# 1-Schematic_KANDA_WEATHER.net
KiCad netlist of a schematic drawn in EasyEDA
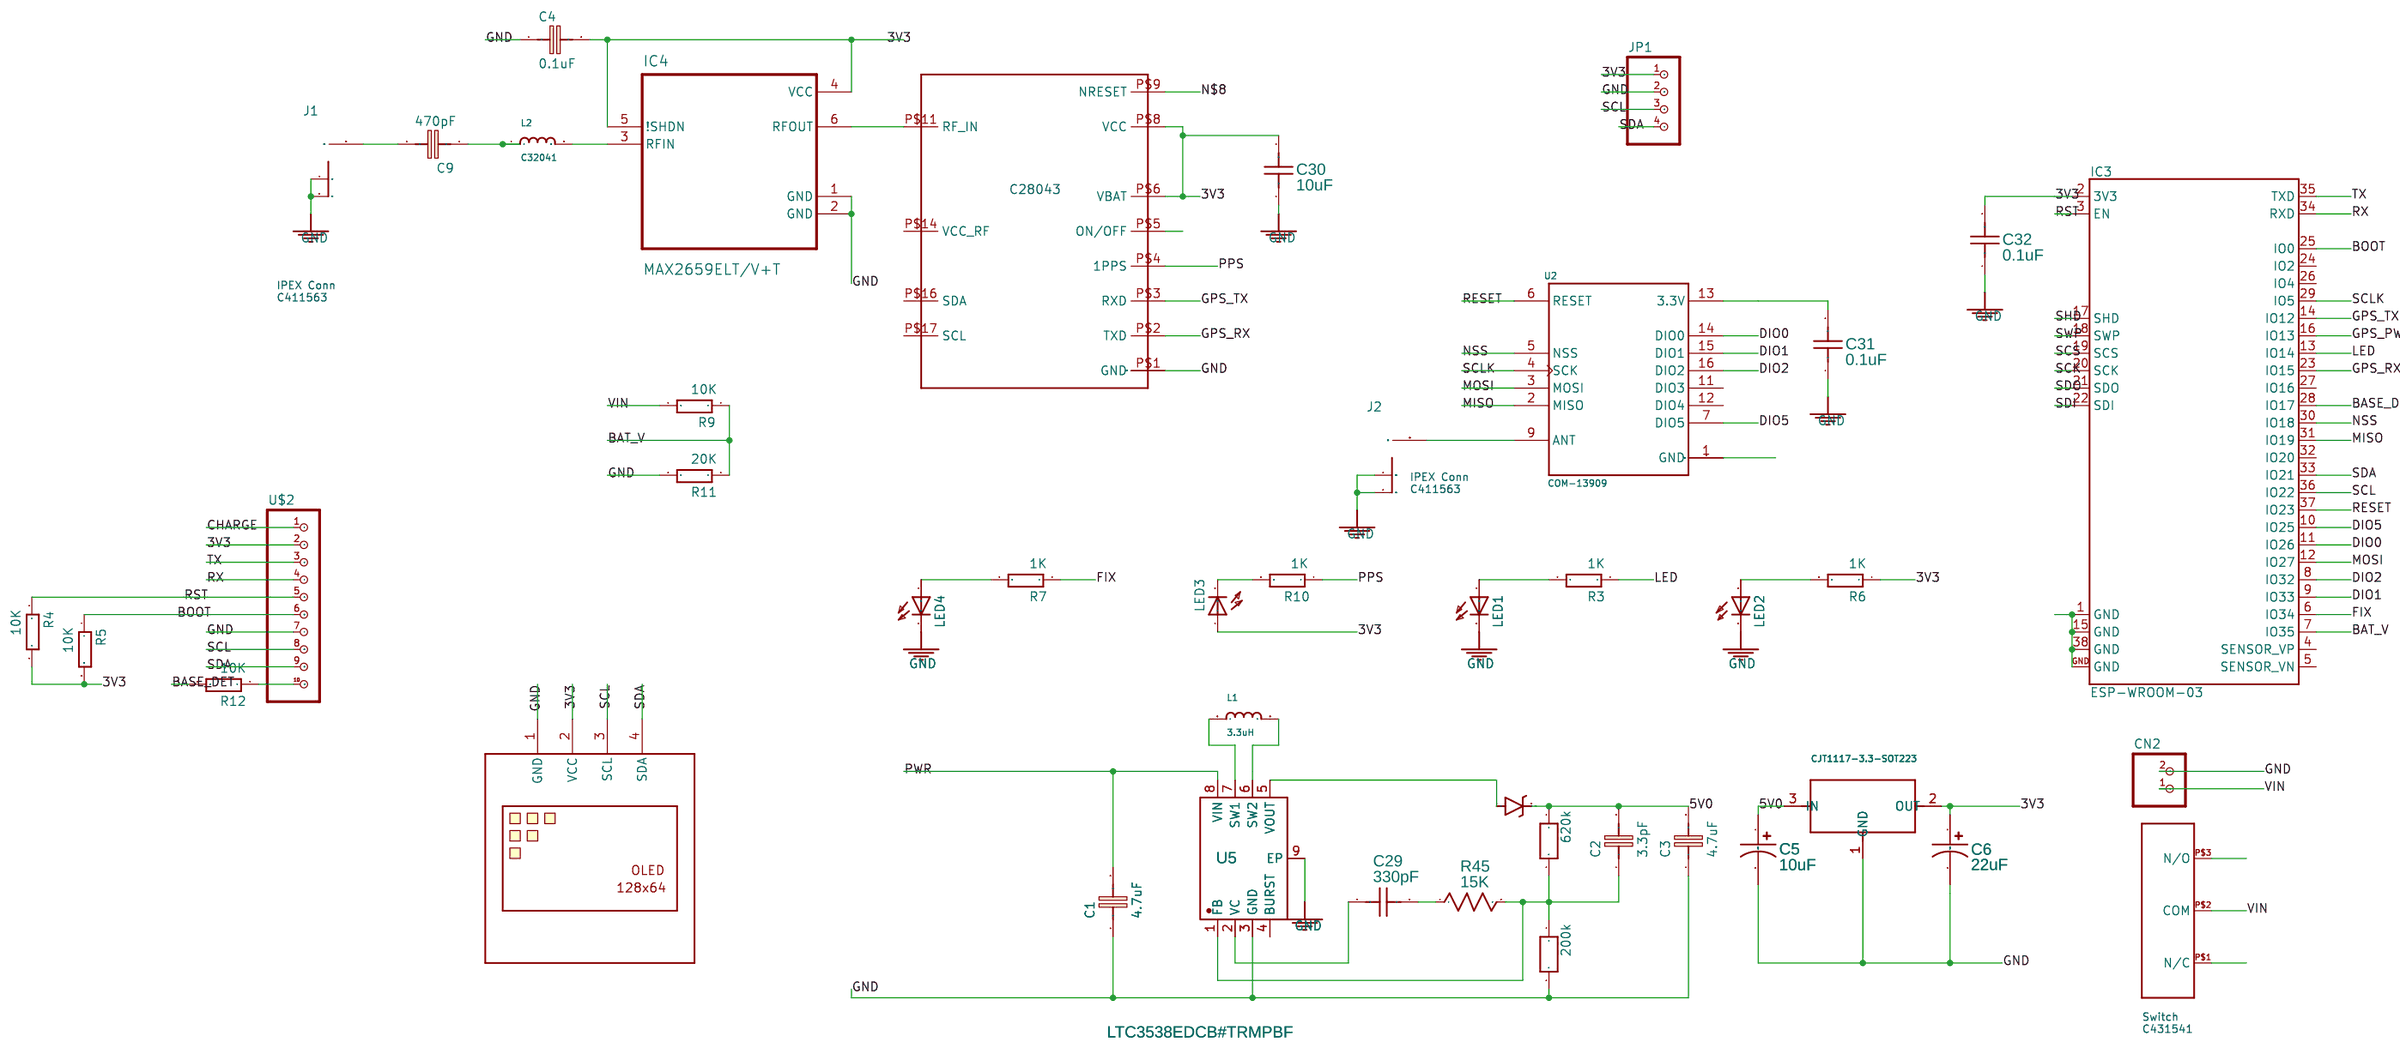
[diagram p0: schematic sheet]

(export (version "E")
  (design (tool "Eeschema 10.0.6"))
  (components
    (comp (ref "C1") (value "4.7uF") (libsource (lib "") (part "Unknown_-210_75")))
    (comp (ref "C2") (value "3.3pF") (libsource (lib "") (part "Unknown_80_40")))
    (comp (ref "C3") (value "4.7uF") (libsource (lib "") (part "Unknown_120_40")))
    (comp (ref "C4") (value "0.1uF") (libsource (lib "") (part "Unknown_-530_-420")))
    (comp (ref "C5") (value "10uF") (libsource (lib "") (part "C_Tan_SMD_A_US")))
    (comp (ref "C6") (value "22uF") (libsource (lib "") (part "C_Tan_SMD_A_US_1")))
    (comp (ref "C9") (value "470pF") (libsource (lib "") (part "Unknown_-600_-360")))
    (comp (ref "C29") (value "330pF") (libsource (lib "") (part "C_0402_US")))
    (comp (ref "C30") (value "10uF") (libsource (lib "") (part "C_0805_US")))
    (comp (ref "C31") (value "0.1uF") (libsource (lib "") (part "C_0603_US")))
    (comp (ref "C32") (value "0.1uF") (libsource (lib "") (part "C_0603_US")))
    (comp (ref "CN2") (value "JST_2PIN-THM") (libsource (lib "") (part "Unknown_400_10")))
    (comp (ref "D1") (value "BA340A") (libsource (lib "") (part "Unknown_20_20")))
    (comp (ref "IC1") (value "CJT1117-3.3-SOT223") (libsource (lib "") (part "Unknown_220_20")))
    (comp (ref "IC3") (value "ESP-WROOM-03") (libsource (lib "") (part "Unknown_410_-200")))
    (comp (ref "IC4") (value "MAX2659ELT/V+T") (libsource (lib "") (part "Unknown_-430_-350")))
    (comp (ref "IC54") (value "ATGM336H") (libsource (lib "") (part "Unknown_-250_-310")))
    (comp (ref "J1") (value "U.FL") (libsource (lib "") (part "Unknown_-660_-360")))
    (comp (ref "J2") (value "U.FL") (libsource (lib "") (part "Unknown_-50_-190")))
    (comp (ref "JP1") (value "HEADER-1X4ROUND") (libsource (lib "") (part "Unknown_110_-380")))
    (comp (ref "L1") (value "3.3uH") (libsource (lib "") (part "Unknown_-135_-30")))
    (comp (ref "L2") (value "C32041") (libsource (lib "") (part "Unknown_-540_-360")))
    (comp (ref "LED1") (value "LEDSML0805") (libsource (lib "") (part "Unknown_0_-100")))
    (comp (ref "LED2") (value "LEDSML0805") (libsource (lib "") (part "Unknown_150_-100")))
    (comp (ref "LED3") (value "LEDSML0805") (libsource (lib "") (part "Unknown_-150_-90")))
    (comp (ref "LED4") (value "LEDSML0805") (libsource (lib "") (part "Unknown_-320_-100")))
    (comp (ref "R1") (value "620k") (libsource (lib "") (part "Unknown_40_40")))
    (comp (ref "R2") (value "200k") (libsource (lib "") (part "Unknown_40_105")))
    (comp (ref "R3") (value "1K") (libsource (lib "") (part "Unknown_60_-110")))
    (comp (ref "R4") (value "10K") (libsource (lib "") (part "Unknown_-830_-80")))
    (comp (ref "R5") (value "10K") (libsource (lib "") (part "Unknown_-800_-70")))
    (comp (ref "R6") (value "1K") (libsource (lib "") (part "Unknown_210_-110")))
    (comp (ref "R7") (value "1K") (libsource (lib "") (part "Unknown_-260_-110")))
    (comp (ref "R9") (value "10K") (libsource (lib "") (part "Unknown_-450_-210")))
    (comp (ref "R10") (value "1K") (libsource (lib "") (part "Unknown_-110_-110")))
    (comp (ref "R11") (value "20K") (libsource (lib "") (part "Unknown_-450_-170")))
    (comp (ref "R12") (value "10K") (libsource (lib "") (part "Unknown_-720_-50")))
    (comp (ref "R45") (value "15K") (libsource (lib "") (part "R_0603_US")))
    (comp (ref "S1") (value "SMD-SWITCH") (libsource (lib "") (part "Unknown_430_80")))
    (comp (ref "U$1") (value "DISPLAY-OLED-128X64-I2C") (libsource (lib "") (part "Unknown_-510_50")))
    (comp (ref "U$2") (value "HEADER-1X10ROUND") (libsource (lib "") (part "Unknown_-670_-100")))
    (comp (ref "U2") (value "COM-13909") (libsource (lib "") (part "Unknown_80_-230")))
    (comp (ref "U5")
      (value "LTC3538EDCB#TRMPBF")
      (fields (field (name "BOM_Supplier Part") "C684931"))
      (libsource (lib "") (part "LTC3538EDCB#TRMPBF"))
    )
  )
  (nets
    (net (code "1") (name "/3V3") (class "Default")
      (node (ref "C30") (pin "2") (pinfunction "2_2") (pintype "unspecified"))
      (node (ref "C32") (pin "2") (pinfunction "2_2") (pintype "unspecified"))
      (node (ref "C4") (pin "2") (pinfunction "2_2") (pintype "bidirectional"))
      (node (ref "C6") (pin "1") (pinfunction "1_1") (pintype "unspecified"))
      (node (ref "IC1") (pin "2") (pinfunction "OUT_2") (pintype "bidirectional"))
      (node (ref "IC3") (pin "2") (pinfunction "3V3_2") (pintype "bidirectional"))
      (node (ref "IC4") (pin "4") (pinfunction "VCC_4") (pintype "bidirectional"))
      (node (ref "IC4") (pin "5") (pinfunction "!SHDN_5") (pintype "bidirectional"))
      (node (ref "IC54") (pin "P$6") (pinfunction "VBAT_P$6") (pintype "bidirectional"))
      (node (ref "IC54") (pin "P$8") (pinfunction "VCC_P$8") (pintype "bidirectional"))
      (node (ref "JP1") (pin "1") (pinfunction "1_1") (pintype "bidirectional"))
      (node (ref "LED3") (pin "A") (pinfunction "A_A") (pintype "bidirectional"))
      (node (ref "R4") (pin "2") (pinfunction "2_2") (pintype "bidirectional"))
      (node (ref "R5") (pin "2") (pinfunction "2_2") (pintype "bidirectional"))
      (node (ref "R6") (pin "1") (pinfunction "1_1") (pintype "bidirectional"))
      (node (ref "U$1") (pin "2") (pinfunction "VCC_2") (pintype "bidirectional"))
      (node (ref "U$2") (pin "2") (pinfunction "2_2") (pintype "bidirectional"))
    )
    (net (code "2") (name "/5V0") (class "Default")
      (node (ref "C2") (pin "2") (pinfunction "2_2") (pintype "bidirectional"))
      (node (ref "C3") (pin "2") (pinfunction "2_2") (pintype "bidirectional"))
      (node (ref "C5") (pin "1") (pinfunction "1_1") (pintype "unspecified"))
      (node (ref "D1") (pin "C") (pinfunction "C_C") (pintype "bidirectional"))
      (node (ref "IC1") (pin "3") (pinfunction "IN_3") (pintype "bidirectional"))
      (node (ref "R1") (pin "1") (pinfunction "1_1") (pintype "bidirectional"))
    )
    (net (code "3") (name "/BASE_DET") (class "Default")
      (node (ref "IC3") (pin "28") (pinfunction "IO17_28") (pintype "bidirectional"))
      (node (ref "R12") (pin "2") (pinfunction "2_2") (pintype "bidirectional"))
    )
    (net (code "4") (name "/BAT_V") (class "Default")
      (node (ref "IC3") (pin "7") (pinfunction "IO35_7") (pintype "bidirectional"))
      (node (ref "R11") (pin "1") (pinfunction "1_1") (pintype "bidirectional"))
      (node (ref "R9") (pin "1") (pinfunction "1_1") (pintype "bidirectional"))
    )
    (net (code "5") (name "/BOOT") (class "Default")
      (node (ref "IC3") (pin "25") (pinfunction "IO0_25") (pintype "bidirectional"))
      (node (ref "R5") (pin "1") (pinfunction "1_1") (pintype "bidirectional"))
      (node (ref "U$2") (pin "6") (pinfunction "6_6") (pintype "bidirectional"))
    )
    (net (code "6") (name "/CHARGE") (class "Default")
      (node (ref "U$2") (pin "1") (pinfunction "1_1") (pintype "bidirectional"))
    )
    (net (code "7") (name "/DIO0") (class "Default")
      (node (ref "IC3") (pin "11") (pinfunction "IO26_11") (pintype "bidirectional"))
      (node (ref "U2") (pin "14") (pinfunction "DIO0_14") (pintype "bidirectional"))
    )
    (net (code "8") (name "/DIO1") (class "Default")
      (node (ref "IC3") (pin "9") (pinfunction "IO33_9") (pintype "bidirectional"))
      (node (ref "U2") (pin "15") (pinfunction "DIO1_15") (pintype "bidirectional"))
    )
    (net (code "9") (name "/DIO2") (class "Default")
      (node (ref "IC3") (pin "8") (pinfunction "IO32_8") (pintype "bidirectional"))
      (node (ref "U2") (pin "16") (pinfunction "DIO2_16") (pintype "bidirectional"))
    )
    (net (code "10") (name "/DIO5") (class "Default")
      (node (ref "IC3") (pin "10") (pinfunction "IO25_10") (pintype "bidirectional"))
      (node (ref "U2") (pin "7") (pinfunction "DIO5_7") (pintype "bidirectional"))
    )
    (net (code "11") (name "/FIX") (class "Default")
      (node (ref "IC3") (pin "6") (pinfunction "IO34_6") (pintype "bidirectional"))
      (node (ref "R7") (pin "1") (pinfunction "1_1") (pintype "bidirectional"))
    )
    (net (code "12") (name "/GPS_PWR") (class "Default")
      (node (ref "IC3") (pin "16") (pinfunction "IO13_16") (pintype "bidirectional"))
    )
    (net (code "13") (name "/GPS_RX") (class "Default")
      (node (ref "IC3") (pin "23") (pinfunction "IO15_23") (pintype "bidirectional"))
      (node (ref "IC54") (pin "P$2") (pinfunction "TXD_P$2") (pintype "bidirectional"))
    )
    (net (code "14") (name "/GPS_TX") (class "Default")
      (node (ref "IC3") (pin "14") (pinfunction "IO12_14") (pintype "bidirectional"))
      (node (ref "IC54") (pin "P$3") (pinfunction "RXD_P$3") (pintype "bidirectional"))
    )
    (net (code "15") (name "/LED") (class "Default")
      (node (ref "IC3") (pin "13") (pinfunction "IO14_13") (pintype "bidirectional"))
      (node (ref "R3") (pin "1") (pinfunction "1_1") (pintype "bidirectional"))
    )
    (net (code "16") (name "/MISO") (class "Default")
      (node (ref "IC3") (pin "31") (pinfunction "IO19_31") (pintype "bidirectional"))
      (node (ref "U2") (pin "2") (pinfunction "MISO_2") (pintype "bidirectional"))
    )
    (net (code "17") (name "/MOSI") (class "Default")
      (node (ref "IC3") (pin "12") (pinfunction "IO27_12") (pintype "bidirectional"))
      (node (ref "U2") (pin "3") (pinfunction "MOSI_3") (pintype "bidirectional"))
    )
    (net (code "18") (name "/N$8") (class "Default")
      (node (ref "IC54") (pin "P$9") (pinfunction "NRESET_P$9") (pintype "bidirectional"))
    )
    (net (code "19") (name "/NSS") (class "Default")
      (node (ref "IC3") (pin "30") (pinfunction "IO18_30") (pintype "bidirectional"))
      (node (ref "U2") (pin "5") (pinfunction "NSS_5") (pintype "bidirectional"))
    )
    (net (code "20") (name "/PPS") (class "Default")
      (node (ref "IC54") (pin "P$4") (pinfunction "1PPS_P$4") (pintype "bidirectional"))
      (node (ref "R10") (pin "1") (pinfunction "1_1") (pintype "bidirectional"))
    )
    (net (code "21") (name "/PWR") (class "Default")
      (node (ref "C1") (pin "2") (pinfunction "2_2") (pintype "bidirectional"))
      (node (ref "U5") (pin "8") (pinfunction "VIN_8") (pintype "unspecified"))
    )
    (net (code "22") (name "/RESET") (class "Default")
      (node (ref "IC3") (pin "37") (pinfunction "IO23_37") (pintype "bidirectional"))
      (node (ref "U2") (pin "6") (pinfunction "RESET_6") (pintype "bidirectional"))
    )
    (net (code "23") (name "/RST") (class "Default")
      (node (ref "IC3") (pin "3") (pinfunction "EN_3") (pintype "bidirectional"))
      (node (ref "R4") (pin "1") (pinfunction "1_1") (pintype "bidirectional"))
      (node (ref "U$2") (pin "5") (pinfunction "5_5") (pintype "bidirectional"))
    )
    (net (code "24") (name "/RX") (class "Default")
      (node (ref "IC3") (pin "34") (pinfunction "RXD_34") (pintype "bidirectional"))
      (node (ref "U$2") (pin "4") (pinfunction "4_4") (pintype "bidirectional"))
    )
    (net (code "25") (name "/SCK") (class "Default")
      (node (ref "IC3") (pin "20") (pinfunction "SCK_20") (pintype "bidirectional"))
    )
    (net (code "26") (name "/SCL") (class "Default")
      (node (ref "IC3") (pin "36") (pinfunction "IO22_36") (pintype "bidirectional"))
      (node (ref "JP1") (pin "3") (pinfunction "3_3") (pintype "bidirectional"))
      (node (ref "U$1") (pin "3") (pinfunction "SCL_3") (pintype "bidirectional"))
      (node (ref "U$2") (pin "8") (pinfunction "8_8") (pintype "bidirectional"))
    )
    (net (code "27") (name "/SCLK") (class "Default")
      (node (ref "IC3") (pin "29") (pinfunction "IO5_29") (pintype "bidirectional"))
      (node (ref "U2") (pin "4") (pinfunction "SCK_4") (pintype "bidirectional"))
    )
    (net (code "28") (name "/SCS") (class "Default")
      (node (ref "IC3") (pin "19") (pinfunction "SCS_19") (pintype "bidirectional"))
    )
    (net (code "29") (name "/SDA") (class "Default")
      (node (ref "IC3") (pin "33") (pinfunction "IO21_33") (pintype "bidirectional"))
      (node (ref "JP1") (pin "4") (pinfunction "4_4") (pintype "bidirectional"))
      (node (ref "U$1") (pin "4") (pinfunction "SDA_4") (pintype "bidirectional"))
      (node (ref "U$2") (pin "9") (pinfunction "9_9") (pintype "bidirectional"))
    )
    (net (code "30") (name "/SDI") (class "Default")
      (node (ref "IC3") (pin "22") (pinfunction "SDI_22") (pintype "bidirectional"))
    )
    (net (code "31") (name "/SDO") (class "Default")
      (node (ref "IC3") (pin "21") (pinfunction "SDO_21") (pintype "bidirectional"))
    )
    (net (code "32") (name "/SHD") (class "Default")
      (node (ref "IC3") (pin "17") (pinfunction "SHD_17") (pintype "bidirectional"))
    )
    (net (code "33") (name "/SWP") (class "Default")
      (node (ref "IC3") (pin "18") (pinfunction "SWP_18") (pintype "bidirectional"))
    )
    (net (code "34") (name "/TX") (class "Default")
      (node (ref "IC3") (pin "35") (pinfunction "TXD_35") (pintype "bidirectional"))
      (node (ref "U$2") (pin "3") (pinfunction "3_3") (pintype "bidirectional"))
    )
    (net (code "35") (name "/VIN") (class "Default")
      (node (ref "CN2") (pin "1") (pinfunction "2_1") (pintype "bidirectional"))
      (node (ref "R9") (pin "2") (pinfunction "2_2") (pintype "bidirectional"))
      (node (ref "S1") (pin "P$2") (pinfunction "COM_P$2") (pintype "bidirectional"))
    )
    (net (code "36") (name "GND") (class "Default")
      (node (ref "C1") (pin "1") (pinfunction "1_1") (pintype "bidirectional"))
      (node (ref "C3") (pin "1") (pinfunction "1_1") (pintype "bidirectional"))
      (node (ref "C30") (pin "1") (pinfunction "1_1") (pintype "unspecified"))
      (node (ref "C31") (pin "1") (pinfunction "1_1") (pintype "unspecified"))
      (node (ref "C32") (pin "1") (pinfunction "1_1") (pintype "unspecified"))
      (node (ref "C4") (pin "1") (pinfunction "1_1") (pintype "bidirectional"))
      (node (ref "C5") (pin "2") (pinfunction "2_2") (pintype "unspecified"))
      (node (ref "C6") (pin "2") (pinfunction "2_2") (pintype "unspecified"))
      (node (ref "CN2") (pin "2") (pinfunction "1_2") (pintype "bidirectional"))
      (node (ref "IC1") (pin "1") (pinfunction "GND_1") (pintype "bidirectional"))
      (node (ref "IC4") (pin "1") (pinfunction "GND_1") (pintype "bidirectional"))
      (node (ref "IC4") (pin "2") (pinfunction "GND_2") (pintype "bidirectional"))
      (node (ref "IC54") (pin "P$1") (pinfunction "GND_P$1") (pintype "bidirectional"))
      (node (ref "IC54") (pin "P$10") (pinfunction "GND_P$10") (pintype "bidirectional"))
      (node (ref "IC54") (pin "P$12") (pinfunction "GND_P$12") (pintype "bidirectional"))
      (node (ref "J1") (pin "1") (pinfunction "GND_1") (pintype "bidirectional"))
      (node (ref "J1") (pin "2") (pinfunction "GND_2") (pintype "bidirectional"))
      (node (ref "J2") (pin "1") (pinfunction "GND_1") (pintype "bidirectional"))
      (node (ref "J2") (pin "2") (pinfunction "GND_2") (pintype "bidirectional"))
      (node (ref "JP1") (pin "2") (pinfunction "2_2") (pintype "bidirectional"))
      (node (ref "LED1") (pin "C") (pinfunction "C_C") (pintype "bidirectional"))
      (node (ref "LED2") (pin "C") (pinfunction "C_C") (pintype "bidirectional"))
      (node (ref "LED4") (pin "C") (pinfunction "C_C") (pintype "bidirectional"))
      (node (ref "R11") (pin "2") (pinfunction "2_2") (pintype "bidirectional"))
      (node (ref "R2") (pin "2") (pinfunction "2_2") (pintype "bidirectional"))
      (node (ref "U$1") (pin "1") (pinfunction "GND_1") (pintype "bidirectional"))
      (node (ref "U$2") (pin "7") (pinfunction "7_7") (pintype "bidirectional"))
      (node (ref "U5") (pin "3") (pinfunction "GND_3") (pintype "unspecified"))
      (node (ref "U5") (pin "9") (pinfunction "EP_9") (pintype "unspecified"))
    )
    (net (code "37") (name "Net-(C9-Pad1)") (class "Default")
      (node (ref "C9") (pin "1") (pinfunction "1_1") (pintype "bidirectional"))
      (node (ref "L2") (pin "1") (pinfunction "1_1") (pintype "bidirectional"))
    )
    (net (code "38") (name "Net-(C29-Pad2)") (class "Default")
      (node (ref "C29") (pin "2") (pinfunction "2_2") (pintype "unspecified"))
      (node (ref "R45") (pin "1") (pinfunction "1_1") (pintype "unspecified"))
    )
    (net (code "39") (name "Net-(IC3-GND-Pad1)") (class "Default")
      (node (ref "IC3") (pin "1") (pinfunction "GND_1") (pintype "bidirectional"))
      (node (ref "IC3") (pin "15") (pinfunction "GND_15") (pintype "bidirectional"))
      (node (ref "IC3") (pin "38") (pinfunction "GND_38") (pintype "bidirectional"))
      (node (ref "IC3") (pin "GND") (pinfunction "GND_GND") (pintype "bidirectional"))
    )
    (net (code "40") (name "Net-(IC4-RFIN)") (class "Default")
      (node (ref "IC4") (pin "3") (pinfunction "RFIN_3") (pintype "bidirectional"))
      (node (ref "L2") (pin "2") (pinfunction "2_2") (pintype "bidirectional"))
    )
    (net (code "41") (name "Net-(IC4-RFOUT)") (class "Default")
      (node (ref "IC4") (pin "6") (pinfunction "RFOUT_6") (pintype "bidirectional"))
      (node (ref "IC54") (pin "P$11") (pinfunction "RF_IN_P$11") (pintype "bidirectional"))
    )
    (net (code "42") (name "Net-(J1-SIGNAL)") (class "Default")
      (node (ref "C9") (pin "2") (pinfunction "2_2") (pintype "bidirectional"))
      (node (ref "J1") (pin "FEED") (pinfunction "SIGNAL_FEED") (pintype "bidirectional"))
    )
    (net (code "43") (name "Net-(J2-SIGNAL)") (class "Default")
      (node (ref "J2") (pin "FEED") (pinfunction "SIGNAL_FEED") (pintype "bidirectional"))
      (node (ref "U2") (pin "9") (pinfunction "ANT_9") (pintype "bidirectional"))
    )
    (net (code "44") (name "Net-(L1-1)") (class "Default")
      (node (ref "L1") (pin "P$1") (pinfunction "1_P$1") (pintype "bidirectional"))
      (node (ref "U5") (pin "7") (pinfunction "SW1_7") (pintype "unspecified"))
    )
    (net (code "45") (name "Net-(L1-2)") (class "Default")
      (node (ref "L1") (pin "P$2") (pinfunction "2_P$2") (pintype "bidirectional"))
      (node (ref "U5") (pin "6") (pinfunction "SW2_6") (pintype "unspecified"))
    )
    (net (code "46") (name "Net-(LED1-PadA)") (class "Default")
      (node (ref "LED1") (pin "A") (pinfunction "A_A") (pintype "bidirectional"))
      (node (ref "R3") (pin "2") (pinfunction "2_2") (pintype "bidirectional"))
    )
    (net (code "47") (name "Net-(LED2-PadA)") (class "Default")
      (node (ref "LED2") (pin "A") (pinfunction "A_A") (pintype "bidirectional"))
      (node (ref "R6") (pin "2") (pinfunction "2_2") (pintype "bidirectional"))
    )
    (net (code "48") (name "Net-(LED3-PadC)") (class "Default")
      (node (ref "LED3") (pin "C") (pinfunction "C_C") (pintype "bidirectional"))
      (node (ref "R10") (pin "2") (pinfunction "2_2") (pintype "bidirectional"))
    )
    (net (code "49") (name "Net-(LED4-PadA)") (class "Default")
      (node (ref "LED4") (pin "A") (pinfunction "A_A") (pintype "bidirectional"))
      (node (ref "R7") (pin "2") (pinfunction "2_2") (pintype "bidirectional"))
    )
    (net (code "50") (name "Net-(R12-Pad1)") (class "Default")
      (node (ref "R12") (pin "1") (pinfunction "1_1") (pintype "bidirectional"))
      (node (ref "U$2") (pin "10") (pinfunction "10_10") (pintype "bidirectional"))
    )
    (net (code "51") (name "Net-(U2-3.3V)") (class "Default")
      (node (ref "C31") (pin "2") (pinfunction "2_2") (pintype "unspecified"))
      (node (ref "U2") (pin "13") (pinfunction "3.3V_13") (pintype "bidirectional"))
    )
    (net (code "52") (name "Net-(U2-GND-Pad1)") (class "Default")
      (node (ref "U2") (pin "1") (pinfunction "GND_1") (pintype "bidirectional"))
      (node (ref "U2") (pin "10") (pinfunction "GND_10") (pintype "bidirectional"))
      (node (ref "U2") (pin "8") (pinfunction "GND_8") (pintype "bidirectional"))
    )
    (net (code "53") (name "Net-(U5-FB)") (class "Default")
      (node (ref "C2") (pin "1") (pinfunction "1_1") (pintype "bidirectional"))
      (node (ref "R1") (pin "2") (pinfunction "2_2") (pintype "bidirectional"))
      (node (ref "R2") (pin "1") (pinfunction "1_1") (pintype "bidirectional"))
      (node (ref "R45") (pin "2") (pinfunction "2_2") (pintype "unspecified"))
      (node (ref "U5") (pin "1") (pinfunction "FB_1") (pintype "unspecified"))
    )
    (net (code "54") (name "Net-(U5-VC)") (class "Default")
      (node (ref "C29") (pin "1") (pinfunction "1_1") (pintype "unspecified"))
      (node (ref "U5") (pin "2") (pinfunction "VC_2") (pintype "unspecified"))
    )
    (net (code "55") (name "Net-(U5-VOUT)") (class "Default")
      (node (ref "D1") (pin "A") (pinfunction "A_A") (pintype "bidirectional"))
      (node (ref "U5") (pin "5") (pinfunction "VOUT_5") (pintype "unspecified"))
    )
    (net (code "56") (name "unconnected-(IC3-IO2-Pad24)") (class "Default")
      (node (ref "IC3") (pin "24") (pinfunction "IO2_24") (pintype "bidirectional"))
    )
    (net (code "57") (name "unconnected-(IC3-IO4-Pad26)") (class "Default")
      (node (ref "IC3") (pin "26") (pinfunction "IO4_26") (pintype "bidirectional"))
    )
    (net (code "58") (name "unconnected-(IC3-IO16-Pad27)") (class "Default")
      (node (ref "IC3") (pin "27") (pinfunction "IO16_27") (pintype "bidirectional"))
    )
    (net (code "59") (name "unconnected-(IC3-IO20-Pad32)") (class "Default")
      (node (ref "IC3") (pin "32") (pinfunction "IO20_32") (pintype "bidirectional"))
    )
    (net (code "60") (name "unconnected-(IC3-SENSOR_VN-Pad5)") (class "Default")
      (node (ref "IC3") (pin "5") (pinfunction "SENSOR_VN_5") (pintype "bidirectional"))
    )
    (net (code "61") (name "unconnected-(IC3-SENSOR_VP-Pad4)") (class "Default")
      (node (ref "IC3") (pin "4") (pinfunction "SENSOR_VP_4") (pintype "bidirectional"))
    )
    (net (code "62") (name "unconnected-(IC54-ON{slash}OFF-PadP$5)") (class "Default")
      (node (ref "IC54") (pin "P$5") (pinfunction "ON/OFF_P$5") (pintype "bidirectional"))
    )
    (net (code "63") (name "unconnected-(IC54-SCL-PadP$17)") (class "Default")
      (node (ref "IC54") (pin "P$17") (pinfunction "SCL_P$17") (pintype "bidirectional"))
    )
    (net (code "64") (name "unconnected-(IC54-SDA-PadP$16)") (class "Default")
      (node (ref "IC54") (pin "P$16") (pinfunction "SDA_P$16") (pintype "bidirectional"))
    )
    (net (code "65") (name "unconnected-(IC54-VCC_RF-PadP$14)") (class "Default")
      (node (ref "IC54") (pin "P$14") (pinfunction "VCC_RF_P$14") (pintype "bidirectional"))
    )
    (net (code "66") (name "unconnected-(S1-N{slash}C-PadP$1)") (class "Default")
      (node (ref "S1") (pin "P$1") (pinfunction "N/C_P$1") (pintype "bidirectional"))
    )
    (net (code "67") (name "unconnected-(S1-N{slash}O-PadP$3)") (class "Default")
      (node (ref "S1") (pin "P$3") (pinfunction "N/O_P$3") (pintype "bidirectional"))
    )
    (net (code "68") (name "unconnected-(U2-DIO3-Pad11)") (class "Default")
      (node (ref "U2") (pin "11") (pinfunction "DIO3_11") (pintype "bidirectional"))
    )
    (net (code "69") (name "unconnected-(U2-DIO4-Pad12)") (class "Default")
      (node (ref "U2") (pin "12") (pinfunction "DIO4_12") (pintype "bidirectional"))
    )
    (net (code "70") (name "unconnected-(U5-BURST-Pad4)") (class "Default")
      (node (ref "U5") (pin "4") (pinfunction "BURST_4") (pintype "unspecified"))
    )
  )
)
